# STM8_DEVELOPMENT_BOARD.net
KiCad netlist of a schematic drawn in Altium Designer
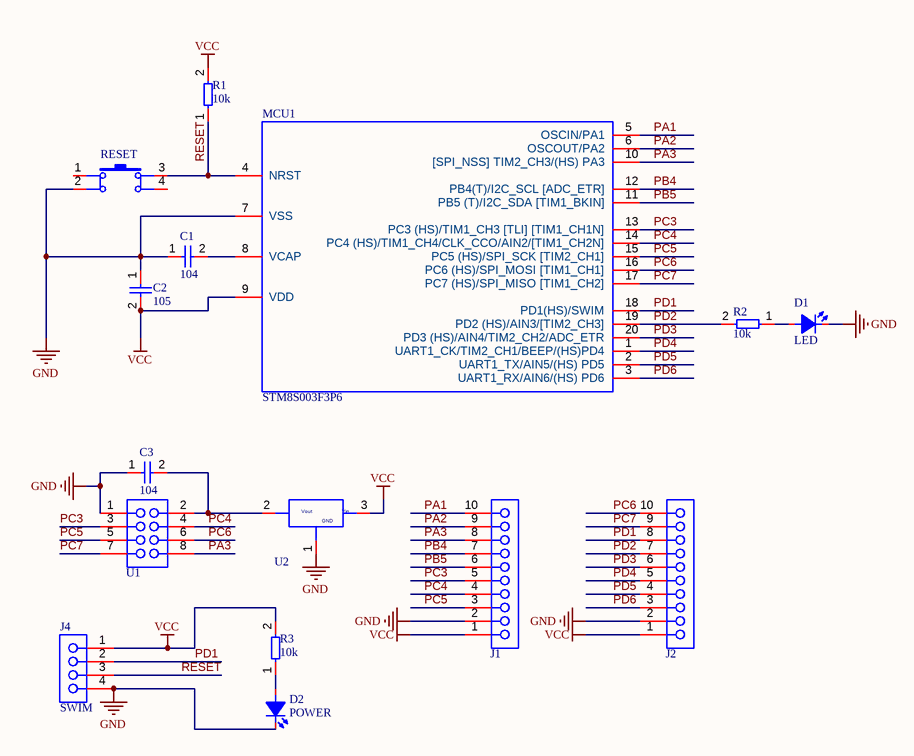
[diagram p0: STM8_DEVELOPMENT_BOARD.SchDoc]

(export (version "E")
  (design (tool "Eeschema 10.0.6"))
  (components
    (comp (ref "C1") (value "104") (footprint "C1206") (libsource (lib "Lib31082020") (part "C1206")))
    (comp (ref "C2") (value "105") (footprint "C1206") (libsource (lib "Lib31082020") (part "C1206")))
    (comp (ref "C3") (value "104") (footprint "C1206") (libsource (lib "Lib31082020") (part "C1206")))
    (comp (ref "D1") (value "LED") (footprint "L0805RED") (libsource (lib "Lib31082020") (part "LED0805")))
    (comp (ref "D2") (value "POWER") (footprint "L0805RED") (libsource (lib "Lib31082020") (part "LED0805")))
    (comp (ref "J1")
      (value "Header 10x1 TH Pitch 2.54mm")
      (footprint "Header 10x1 TH Pitch 2.54mm")
      (libsource (lib "Lib31082020") (part "Header 10x1 TH Pitch 2.54mm"))
    )
    (comp (ref "J2")
      (value "Header 10x1 TH Pitch 2.54mm")
      (footprint "Header 10x1 TH Pitch 2.54mm")
      (libsource (lib "Lib31082020") (part "Header 10x1 TH Pitch 2.54mm"))
    )
    (comp (ref "J4")
      (value "SWIM")
      (footprint "HEADER 2_54 HORIZONTAL 4X")
      (libsource (lib "Lib31082020") (part "Header 4x1 TH Pitch 2.54mm"))
    )
    (comp (ref "MCU1")
      (value "STM8S003F3P6")
      (footprint "TSSOP20_0.65_4.4")
      (libsource (lib "Lib31082020") (part "STM8S003F3P6"))
    )
    (comp (ref "R1") (value "10k") (footprint "R0805") (libsource (lib "Lib31082020") (part "Resistor SMD")))
    (comp (ref "R2") (value "10k") (footprint "R0805") (libsource (lib "") (part "Resistor SMD_1")))
    (comp (ref "R3") (value "10k") (footprint "R0805") (libsource (lib "Lib31082020") (part "Resistor SMD")))
    (comp (ref "SW1")
      (value "RESET")
      (footprint "BUTTON_HOLE_5.0mm")
      (libsource (lib "Lib31082020") (part "Button Hole"))
    )
    (comp (ref "U1")
      (value "nRF24L01")
      (footprint "Header 4x2 TH Pitch 2.54mm")
      (libsource (lib "Lib31082020") (part "Header 4x2 TH Pitch 2.54mm"))
    )
    (comp (ref "U2")
      (value "AMS1117")
      (footprint "SOT223-3")
      (libsource (lib "Lib31082020") (part "AMS1117(SOT-223)"))
    )
  )
  (nets
    (net (code "1") (name "/PA1") (class "Default")
      (node (ref "J1") (pin "10") (pinfunction "10_10") (pintype "passive"))
      (node (ref "MCU1") (pin "5") (pinfunction "OSCIN/PA1_5") (pintype "passive"))
    )
    (net (code "2") (name "/PA2") (class "Default")
      (node (ref "J1") (pin "9") (pinfunction "9_9") (pintype "passive"))
      (node (ref "MCU1") (pin "6") (pinfunction "OSCOUT/PA2_6") (pintype "passive"))
    )
    (net (code "3") (name "/PA3") (class "Default")
      (node (ref "J1") (pin "8") (pinfunction "8_8") (pintype "passive"))
      (node (ref "MCU1") (pin "10") (pinfunction "[SPI_NSS]_TIM2_CH3/(HS)_PA3_10") (pintype "passive"))
      (node (ref "U1") (pin "8") (pinfunction "8_8") (pintype "passive"))
    )
    (net (code "4") (name "/PB4") (class "Default")
      (node (ref "J1") (pin "7") (pinfunction "7_7") (pintype "passive"))
      (node (ref "MCU1") (pin "12") (pinfunction "PB4(T)/I2C_SCL_[ADC_ETR]_12") (pintype "passive"))
    )
    (net (code "5") (name "/PB5") (class "Default")
      (node (ref "J1") (pin "6") (pinfunction "6_6") (pintype "passive"))
      (node (ref "MCU1") (pin "11") (pinfunction "PB5_(T)/I2C_SDA_[TIM1_BKIN]_11") (pintype "passive"))
    )
    (net (code "6") (name "/PC3") (class "Default")
      (node (ref "J1") (pin "5") (pinfunction "5_5") (pintype "passive"))
      (node (ref "MCU1") (pin "13") (pinfunction "PC3_(HS)/TIM1_CH3_[TLI]_[TIM1_CH1N]_13") (pintype "passive"))
      (node (ref "U1") (pin "3") (pinfunction "3_3") (pintype "passive"))
    )
    (net (code "7") (name "/PC4") (class "Default")
      (node (ref "J1") (pin "4") (pinfunction "4_4") (pintype "passive"))
      (node (ref "MCU1") (pin "14") (pinfunction "PC4_(HS)/TIM1_CH4/CLK_CCO/AIN2/[TIM1_CH2N]_14") (pintype "passive"))
      (node (ref "U1") (pin "4") (pinfunction "4_4") (pintype "passive"))
    )
    (net (code "8") (name "/PC5") (class "Default")
      (node (ref "J1") (pin "3") (pinfunction "3_3") (pintype "passive"))
      (node (ref "MCU1") (pin "15") (pinfunction "PC5_(HS)/SPI_SCK_[TIM2_CH1]_15") (pintype "passive"))
      (node (ref "U1") (pin "5") (pinfunction "5_5") (pintype "passive"))
    )
    (net (code "9") (name "/PC6") (class "Default")
      (node (ref "J2") (pin "10") (pinfunction "10_10") (pintype "passive"))
      (node (ref "MCU1") (pin "16") (pinfunction "PC6_(HS)/SPI_MOSI_[TIM1_CH1]_16") (pintype "passive"))
      (node (ref "U1") (pin "6") (pinfunction "6_6") (pintype "passive"))
    )
    (net (code "10") (name "/PC7") (class "Default")
      (node (ref "J2") (pin "9") (pinfunction "9_9") (pintype "passive"))
      (node (ref "MCU1") (pin "17") (pinfunction "PC7_(HS)/SPI_MISO_[TIM1_CH2]_17") (pintype "passive"))
      (node (ref "U1") (pin "7") (pinfunction "7_7") (pintype "passive"))
    )
    (net (code "11") (name "/PD1") (class "Default")
      (node (ref "J2") (pin "8") (pinfunction "8_8") (pintype "passive"))
      (node (ref "J4") (pin "2") (pinfunction "2_2") (pintype "passive"))
      (node (ref "MCU1") (pin "18") (pinfunction "PD1(HS)/SWIM_18") (pintype "passive"))
    )
    (net (code "12") (name "/PD2") (class "Default")
      (node (ref "J2") (pin "7") (pinfunction "7_7") (pintype "passive"))
      (node (ref "MCU1") (pin "19") (pinfunction "PD2_(HS)/AIN3/[TIM2_CH3]_19") (pintype "passive"))
      (node (ref "R2") (pin "2") (pinfunction "2_2") (pintype "passive"))
    )
    (net (code "13") (name "/PD3") (class "Default")
      (node (ref "J2") (pin "6") (pinfunction "6_6") (pintype "passive"))
      (node (ref "MCU1") (pin "20") (pinfunction "PD3_(HS)/AIN4/TIM2_CH2/ADC_ETR_20") (pintype "passive"))
    )
    (net (code "14") (name "/PD4") (class "Default")
      (node (ref "J2") (pin "5") (pinfunction "5_5") (pintype "passive"))
      (node (ref "MCU1") (pin "1") (pinfunction "UART1_CK/TIM2_CH1/BEEP/(HS)PD4_1") (pintype "passive"))
    )
    (net (code "15") (name "/PD5") (class "Default")
      (node (ref "J2") (pin "4") (pinfunction "4_4") (pintype "passive"))
      (node (ref "MCU1") (pin "2") (pinfunction "UART1_TX/AIN5/(HS)_PD5_2") (pintype "passive"))
    )
    (net (code "16") (name "/PD6") (class "Default")
      (node (ref "J2") (pin "3") (pinfunction "3_3") (pintype "passive"))
      (node (ref "MCU1") (pin "3") (pinfunction "UART1_RX/AIN6/(HS)_PD6_3") (pintype "passive"))
    )
    (net (code "17") (name "/RESET") (class "Default")
      (node (ref "J4") (pin "3") (pinfunction "3_3") (pintype "passive"))
      (node (ref "MCU1") (pin "4") (pinfunction "NRST_4") (pintype "passive"))
      (node (ref "R1") (pin "1") (pinfunction "1_1") (pintype "passive"))
      (node (ref "SW1") (pin "3") (pinfunction "3_3") (pintype "passive"))
    )
    (net (code "18") (name "GND") (class "Default")
      (node (ref "C1") (pin "1") (pinfunction "1_1") (pintype "passive"))
      (node (ref "C2") (pin "1") (pinfunction "1_1") (pintype "passive"))
      (node (ref "C3") (pin "1") (pinfunction "1_1") (pintype "passive"))
      (node (ref "D1") (pin "2") (pinfunction "K_2") (pintype "passive"))
      (node (ref "D2") (pin "2") (pinfunction "K_2") (pintype "passive"))
      (node (ref "J1") (pin "2") (pinfunction "2_2") (pintype "passive"))
      (node (ref "J2") (pin "2") (pinfunction "2_2") (pintype "passive"))
      (node (ref "J4") (pin "4") (pinfunction "4_4") (pintype "passive"))
      (node (ref "MCU1") (pin "7") (pinfunction "VSS_7") (pintype "passive"))
      (node (ref "SW1") (pin "2") (pinfunction "2_2") (pintype "passive"))
      (node (ref "U1") (pin "1") (pinfunction "1_1") (pintype "passive"))
      (node (ref "U2") (pin "1") (pinfunction "1_1") (pintype "passive"))
    )
    (net (code "19") (name "Net-(C3-Pad2)") (class "Default")
      (node (ref "C3") (pin "2") (pinfunction "2_2") (pintype "passive"))
      (node (ref "U1") (pin "2") (pinfunction "2_2") (pintype "passive"))
      (node (ref "U2") (pin "2") (pinfunction "2_2") (pintype "passive"))
    )
    (net (code "20") (name "Net-(D1-A)") (class "Default")
      (node (ref "D1") (pin "1") (pinfunction "A_1") (pintype "passive"))
      (node (ref "R2") (pin "1") (pinfunction "1_1") (pintype "passive"))
    )
    (net (code "21") (name "Net-(D2-A)") (class "Default")
      (node (ref "D2") (pin "1") (pinfunction "A_1") (pintype "passive"))
      (node (ref "R3") (pin "1") (pinfunction "1_1") (pintype "passive"))
    )
    (net (code "22") (name "Net-(MCU1-VCAP)") (class "Default")
      (node (ref "C1") (pin "2") (pinfunction "2_2") (pintype "passive"))
      (node (ref "MCU1") (pin "8") (pinfunction "VCAP_8") (pintype "passive"))
    )
    (net (code "23") (name "VCC") (class "Default")
      (node (ref "C2") (pin "2") (pinfunction "2_2") (pintype "passive"))
      (node (ref "J1") (pin "1") (pinfunction "1_1") (pintype "passive"))
      (node (ref "J2") (pin "1") (pinfunction "1_1") (pintype "passive"))
      (node (ref "J4") (pin "1") (pinfunction "1_1") (pintype "passive"))
      (node (ref "MCU1") (pin "9") (pinfunction "VDD_9") (pintype "passive"))
      (node (ref "R1") (pin "2") (pinfunction "2_2") (pintype "passive"))
      (node (ref "R3") (pin "2") (pinfunction "2_2") (pintype "passive"))
      (node (ref "U2") (pin "3") (pinfunction "3_3") (pintype "passive"))
    )
    (net (code "24") (name "unconnected-(SW1-Pad1)") (class "Default")
      (node (ref "SW1") (pin "1") (pinfunction "1_1") (pintype "passive"))
    )
    (net (code "25") (name "unconnected-(SW1-Pad4)") (class "Default")
      (node (ref "SW1") (pin "4") (pinfunction "4_4") (pintype "passive"))
    )
  )
)
